# KM2.net
KiCad netlist of a schematic drawn in EAGLE
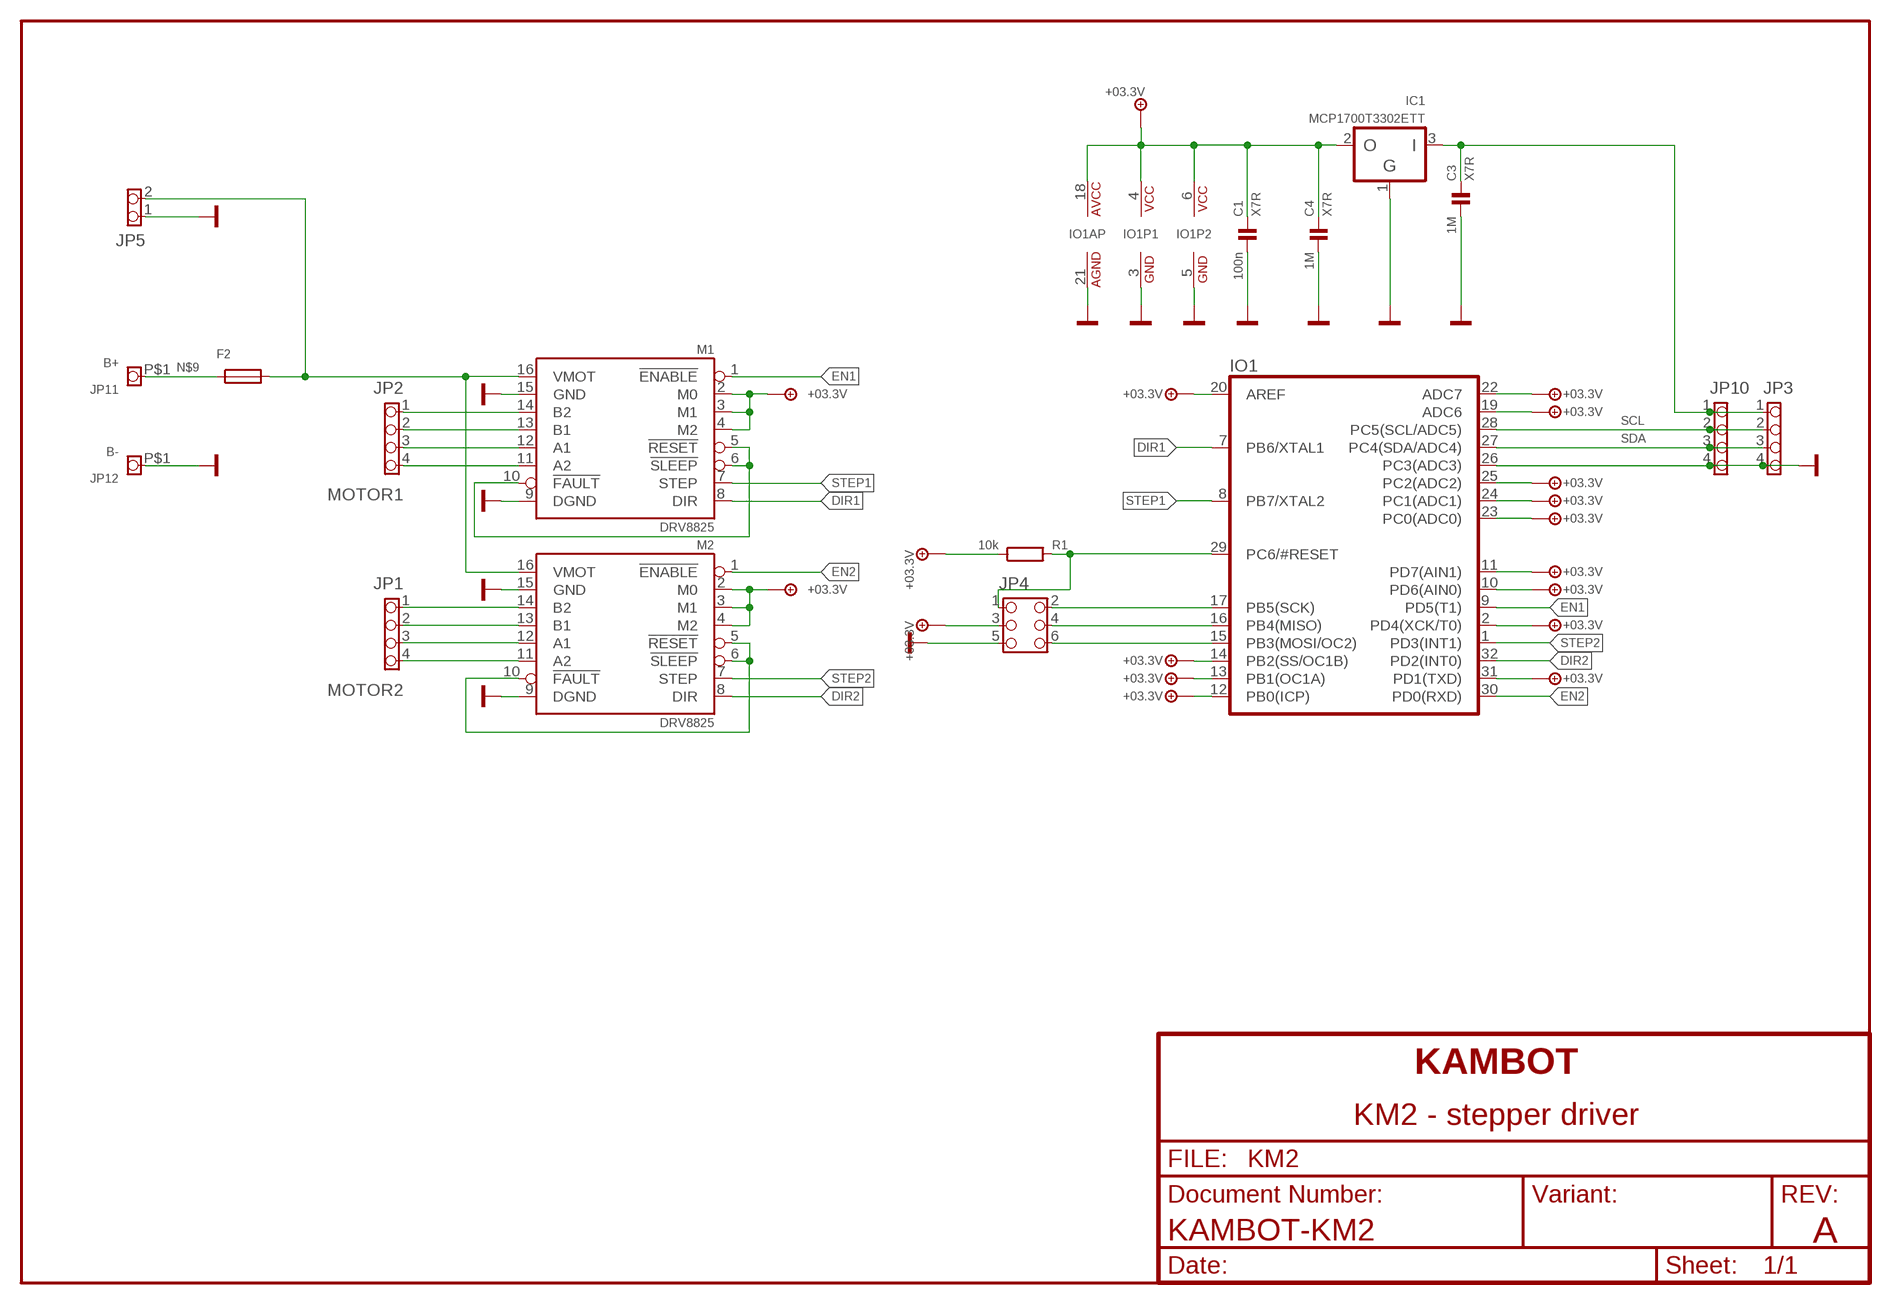
[diagram p0: schematic, sheet 1]

(export (version "E")
  (design (tool "Eeschema 10.0.6"))
  (components
    (comp (ref "C1")
      (value "100n")
      (footprint "eagle-import:0805")
      (libsource (lib "eagle-import") (part "C0805"))
    )
    (comp (ref "C3")
      (value "1M")
      (footprint "eagle-import:0805")
      (libsource (lib "eagle-import") (part "C0805"))
    )
    (comp (ref "C4")
      (value "1M")
      (footprint "eagle-import:0805")
      (libsource (lib "eagle-import") (part "C0805"))
    )
    (comp (ref "F2")
      (value "F_1812")
      (footprint "eagle-import:1812")
      (libsource (lib "eagle-import") (part "F_1812"))
    )
    (comp (ref "IC1")
      (value "MCP1700T3302ETT")
      (footprint "eagle-import:SOT23")
      (libsource (lib "eagle-import") (part "STAB_IO_SOT23_GOI"))
    )
    (comp (ref "IO1")
      (value "MEGA8")
      (footprint "eagle-import:TQFP32")
      (libsource (lib "eagle-import") (part "MEGA8"))
    )
    (comp (ref "JP1")
      (value "MOTOR2")
      (footprint "eagle-import:1X04_254_EDGE")
      (libsource (lib "eagle-import") (part "PINHD-1X4_254_EDGE"))
    )
    (comp (ref "JP2")
      (value "MOTOR1")
      (footprint "eagle-import:1X04_254_EDGE")
      (libsource (lib "eagle-import") (part "PINHD-1X4_254_EDGE"))
    )
    (comp (ref "JP3")
      (value "PINHD-1X4_250_MX5267")
      (footprint "eagle-import:1X04_250_MX5267")
      (libsource (lib "eagle-import") (part "PINHD-1X4_250_MX5267"))
    )
    (comp (ref "JP4")
      (value "PINHD-2X3_254_FP")
      (footprint "eagle-import:2X03_254_FP")
      (libsource (lib "eagle-import") (part "PINHD-2X3_254_FP"))
    )
    (comp (ref "JP5")
      (value "PINHD-1X2_250_MX5267")
      (footprint "eagle-import:1X02_250_MX5267")
      (libsource (lib "eagle-import") (part "PINHD-1X2_250_MX5267"))
    )
    (comp (ref "JP10")
      (value "PINHD-1X4_250_MX5267")
      (footprint "eagle-import:1X04_250_MX5267")
      (libsource (lib "eagle-import") (part "PINHD-1X4_250_MX5267"))
    )
    (comp (ref "JP11")
      (value "B+")
      (footprint "eagle-import:1X01_254_254_PAD")
      (libsource (lib "eagle-import") (part "PINHD-1X1_254X254PAD"))
    )
    (comp (ref "JP12")
      (value "B-")
      (footprint "eagle-import:1X01_254_254_PAD")
      (libsource (lib "eagle-import") (part "PINHD-1X1_254X254PAD"))
    )
    (comp (ref "M1")
      (value "DRV8825")
      (footprint "eagle-import:MODULE_16P")
      (libsource (lib "eagle-import") (part "DRV8825"))
    )
    (comp (ref "M2")
      (value "DRV8825")
      (footprint "eagle-import:MODULE_16P")
      (libsource (lib "eagle-import") (part "DRV8825"))
    )
    (comp (ref "R1")
      (value "10k")
      (footprint "eagle-import:0805")
      (libsource (lib "eagle-import") (part "R_R0805"))
    )
  )
  (nets
    (net (code "1") (name "+03.3V") (class "Default")
      (node (ref "C1") (pin "1") (pinfunction "1_1") (pintype "passive"))
      (node (ref "C4") (pin "1") (pinfunction "1_1") (pintype "passive"))
      (node (ref "IC1") (pin "2") (pinfunction "OUT_2") (pintype "passive"))
      (node (ref "IO1") (pin "10") (pinfunction "PD6(AIN0)_10") (pintype "passive"))
      (node (ref "IO1") (pin "11") (pinfunction "PD7(AIN1)_11") (pintype "passive"))
      (node (ref "IO1") (pin "12") (pinfunction "PB0(ICP)_12") (pintype "passive"))
      (node (ref "IO1") (pin "13") (pinfunction "PB1(OC1A)_13") (pintype "passive"))
      (node (ref "IO1") (pin "14") (pinfunction "PB2(SS/OC1B)_14") (pintype "passive"))
      (node (ref "IO1") (pin "18") (pinfunction "VCC_18") (pintype "passive"))
      (node (ref "IO1") (pin "19") (pinfunction "ADC6_19") (pintype "passive"))
      (node (ref "IO1") (pin "2") (pinfunction "PD4(XCK/T0)_2") (pintype "passive"))
      (node (ref "IO1") (pin "20") (pinfunction "AREF_20") (pintype "passive"))
      (node (ref "IO1") (pin "22") (pinfunction "ADC7_22") (pintype "passive"))
      (node (ref "IO1") (pin "23") (pinfunction "PC0(ADC0)_23") (pintype "passive"))
      (node (ref "IO1") (pin "24") (pinfunction "PC1(ADC1)_24") (pintype "passive"))
      (node (ref "IO1") (pin "25") (pinfunction "PC2(ADC2)_25") (pintype "passive"))
      (node (ref "IO1") (pin "31") (pinfunction "PD1(TXD)_31") (pintype "passive"))
      (node (ref "IO1") (pin "4") (pinfunction "VCC_4") (pintype "passive"))
      (node (ref "IO1") (pin "6") (pinfunction "VCC_6") (pintype "passive"))
      (node (ref "JP4") (pin "3") (pinfunction "3_3") (pintype "passive"))
      (node (ref "M1") (pin "2") (pinfunction "M0_2") (pintype "passive"))
      (node (ref "M1") (pin "3") (pinfunction "M1_3") (pintype "passive"))
      (node (ref "M1") (pin "4") (pinfunction "M2_4") (pintype "passive"))
      (node (ref "M2") (pin "2") (pinfunction "M0_2") (pintype "passive"))
      (node (ref "M2") (pin "3") (pinfunction "M1_3") (pintype "passive"))
      (node (ref "M2") (pin "4") (pinfunction "M2_4") (pintype "passive"))
      (node (ref "R1") (pin "1") (pinfunction "1_1") (pintype "passive"))
    )
    (net (code "2") (name "/N$9") (class "Default")
      (node (ref "F2") (pin "1") (pinfunction "1_1") (pintype "passive"))
      (node (ref "JP11") (pin "P$1") (pinfunction "1_P$1") (pintype "passive"))
    )
    (net (code "3") (name "/SCL") (class "Default")
      (node (ref "IO1") (pin "28") (pinfunction "PC5(SCL/ADC5)_28") (pintype "passive"))
      (node (ref "JP10") (pin "2") (pinfunction "2_2") (pintype "passive"))
      (node (ref "JP3") (pin "2") (pinfunction "2_2") (pintype "passive"))
    )
    (net (code "4") (name "/SDA") (class "Default")
      (node (ref "IO1") (pin "27") (pinfunction "PC4(SDA/ADC4)_27") (pintype "passive"))
      (node (ref "JP10") (pin "3") (pinfunction "3_3") (pintype "passive"))
      (node (ref "JP3") (pin "3") (pinfunction "3_3") (pintype "passive"))
    )
    (net (code "5") (name "DIR1") (class "Default")
      (node (ref "IO1") (pin "7") (pinfunction "PB6/XTAL1_7") (pintype "passive"))
      (node (ref "M1") (pin "8") (pinfunction "DIR_8") (pintype "passive"))
    )
    (net (code "6") (name "DIR2") (class "Default")
      (node (ref "IO1") (pin "32") (pinfunction "PD2(INT0)_32") (pintype "passive"))
      (node (ref "M2") (pin "8") (pinfunction "DIR_8") (pintype "passive"))
    )
    (net (code "7") (name "EN1") (class "Default")
      (node (ref "IO1") (pin "9") (pinfunction "PD5(T1)_9") (pintype "passive"))
      (node (ref "M1") (pin "1") (pinfunction "~{ENABLE}_1") (pintype "passive"))
    )
    (net (code "8") (name "EN2") (class "Default")
      (node (ref "IO1") (pin "30") (pinfunction "PD0(RXD)_30") (pintype "passive"))
      (node (ref "M2") (pin "1") (pinfunction "~{ENABLE}_1") (pintype "passive"))
    )
    (net (code "9") (name "GND") (class "Default")
      (node (ref "C1") (pin "2") (pinfunction "2_2") (pintype "passive"))
      (node (ref "C3") (pin "2") (pinfunction "2_2") (pintype "passive"))
      (node (ref "C4") (pin "2") (pinfunction "2_2") (pintype "passive"))
      (node (ref "IC1") (pin "1") (pinfunction "GND_1") (pintype "passive"))
      (node (ref "IO1") (pin "21") (pinfunction "GND_21") (pintype "passive"))
      (node (ref "IO1") (pin "26") (pinfunction "PC3(ADC3)_26") (pintype "passive"))
      (node (ref "IO1") (pin "3") (pinfunction "GND_3") (pintype "power_in"))
      (node (ref "IO1") (pin "5") (pinfunction "GND_5") (pintype "power_in"))
      (node (ref "JP10") (pin "4") (pinfunction "4_4") (pintype "passive"))
      (node (ref "JP12") (pin "P$1") (pinfunction "1_P$1") (pintype "passive"))
      (node (ref "JP3") (pin "4") (pinfunction "4_4") (pintype "passive"))
      (node (ref "JP4") (pin "5") (pinfunction "5_5") (pintype "passive"))
      (node (ref "JP5") (pin "1") (pinfunction "1_1") (pintype "passive"))
      (node (ref "M1") (pin "15") (pinfunction "GND_15") (pintype "passive"))
      (node (ref "M1") (pin "9") (pinfunction "DGND_9") (pintype "passive"))
      (node (ref "M2") (pin "15") (pinfunction "GND_15") (pintype "passive"))
      (node (ref "M2") (pin "9") (pinfunction "DGND_9") (pintype "passive"))
    )
    (net (code "10") (name "Net-(IC1-IN)") (class "Default")
      (node (ref "C3") (pin "1") (pinfunction "1_1") (pintype "passive"))
      (node (ref "IC1") (pin "3") (pinfunction "IN_3") (pintype "passive"))
      (node (ref "JP10") (pin "1") (pinfunction "1_1") (pintype "passive"))
      (node (ref "JP3") (pin "1") (pinfunction "1_1") (pintype "passive"))
    )
    (net (code "11") (name "Net-(IO1A-PB3(MOSI{slash}OC2))") (class "Default")
      (node (ref "IO1") (pin "15") (pinfunction "PB3(MOSI/OC2)_15") (pintype "passive"))
      (node (ref "JP4") (pin "6") (pinfunction "6_6") (pintype "passive"))
    )
    (net (code "12") (name "Net-(IO1A-PB4(MISO))") (class "Default")
      (node (ref "IO1") (pin "16") (pinfunction "PB4(MISO)_16") (pintype "passive"))
      (node (ref "JP4") (pin "4") (pinfunction "4_4") (pintype "passive"))
    )
    (net (code "13") (name "Net-(IO1A-PB5(SCK))") (class "Default")
      (node (ref "IO1") (pin "17") (pinfunction "PB5(SCK)_17") (pintype "passive"))
      (node (ref "JP4") (pin "2") (pinfunction "2_2") (pintype "passive"))
    )
    (net (code "14") (name "Net-(IO1A-PC6{slash}#RESET)") (class "Default")
      (node (ref "IO1") (pin "29") (pinfunction "PC6/#RESET_29") (pintype "passive"))
      (node (ref "JP4") (pin "1") (pinfunction "1_1") (pintype "passive"))
      (node (ref "R1") (pin "2") (pinfunction "2_2") (pintype "passive"))
    )
    (net (code "15") (name "Net-(M1-A1)") (class "Default")
      (node (ref "JP2") (pin "3") (pinfunction "3_3") (pintype "passive"))
      (node (ref "M1") (pin "12") (pinfunction "A1_12") (pintype "passive"))
    )
    (net (code "16") (name "Net-(M1-A2)") (class "Default")
      (node (ref "JP2") (pin "4") (pinfunction "4_4") (pintype "passive"))
      (node (ref "M1") (pin "11") (pinfunction "A2_11") (pintype "passive"))
    )
    (net (code "17") (name "Net-(M1-B1)") (class "Default")
      (node (ref "JP2") (pin "2") (pinfunction "2_2") (pintype "passive"))
      (node (ref "M1") (pin "13") (pinfunction "B1_13") (pintype "passive"))
    )
    (net (code "18") (name "Net-(M1-B2)") (class "Default")
      (node (ref "JP2") (pin "1") (pinfunction "1_1") (pintype "passive"))
      (node (ref "M1") (pin "14") (pinfunction "B2_14") (pintype "passive"))
    )
    (net (code "19") (name "Net-(M1-VMOT)") (class "Default")
      (node (ref "F2") (pin "2") (pinfunction "2_2") (pintype "passive"))
      (node (ref "JP5") (pin "2") (pinfunction "2_2") (pintype "passive"))
      (node (ref "M1") (pin "16") (pinfunction "VMOT_16") (pintype "passive"))
      (node (ref "M2") (pin "16") (pinfunction "VMOT_16") (pintype "passive"))
    )
    (net (code "20") (name "Net-(M1-~{FAULT})") (class "Default")
      (node (ref "M1") (pin "10") (pinfunction "~{FAULT}_10") (pintype "passive"))
      (node (ref "M1") (pin "5") (pinfunction "~{RESET}_5") (pintype "passive"))
      (node (ref "M1") (pin "6") (pinfunction "~{SLEEP}_6") (pintype "passive"))
    )
    (net (code "21") (name "Net-(M2-A1)") (class "Default")
      (node (ref "JP1") (pin "3") (pinfunction "3_3") (pintype "passive"))
      (node (ref "M2") (pin "12") (pinfunction "A1_12") (pintype "passive"))
    )
    (net (code "22") (name "Net-(M2-A2)") (class "Default")
      (node (ref "JP1") (pin "4") (pinfunction "4_4") (pintype "passive"))
      (node (ref "M2") (pin "11") (pinfunction "A2_11") (pintype "passive"))
    )
    (net (code "23") (name "Net-(M2-B1)") (class "Default")
      (node (ref "JP1") (pin "2") (pinfunction "2_2") (pintype "passive"))
      (node (ref "M2") (pin "13") (pinfunction "B1_13") (pintype "passive"))
    )
    (net (code "24") (name "Net-(M2-B2)") (class "Default")
      (node (ref "JP1") (pin "1") (pinfunction "1_1") (pintype "passive"))
      (node (ref "M2") (pin "14") (pinfunction "B2_14") (pintype "passive"))
    )
    (net (code "25") (name "Net-(M2-~{FAULT})") (class "Default")
      (node (ref "M2") (pin "10") (pinfunction "~{FAULT}_10") (pintype "passive"))
      (node (ref "M2") (pin "5") (pinfunction "~{RESET}_5") (pintype "passive"))
      (node (ref "M2") (pin "6") (pinfunction "~{SLEEP}_6") (pintype "passive"))
    )
    (net (code "26") (name "STEP1") (class "Default")
      (node (ref "IO1") (pin "8") (pinfunction "PB7/XTAL2_8") (pintype "passive"))
      (node (ref "M1") (pin "7") (pinfunction "STEP_7") (pintype "passive"))
    )
    (net (code "27") (name "STEP2") (class "Default")
      (node (ref "IO1") (pin "1") (pinfunction "PD3(INT1)_1") (pintype "passive"))
      (node (ref "M2") (pin "7") (pinfunction "STEP_7") (pintype "passive"))
    )
  )
)
